# MCU_USB_v0.net
KiCad netlist of a schematic drawn in Altium Designer
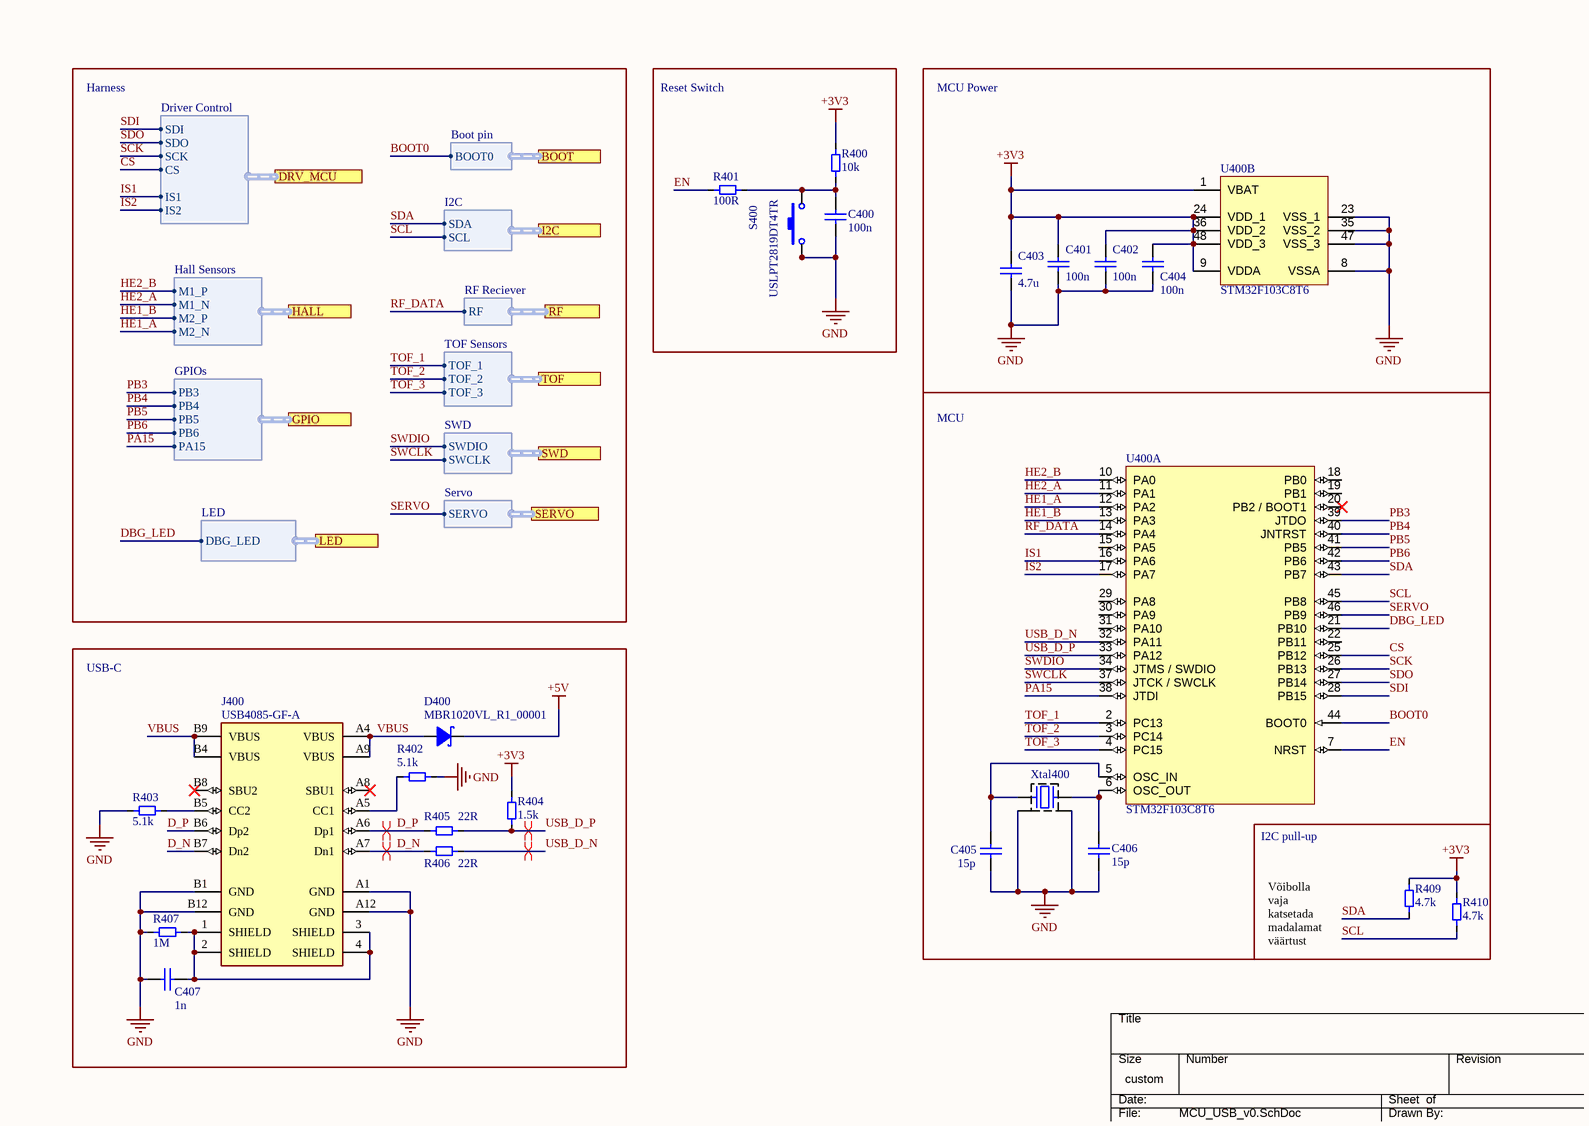
[diagram p0: MCU_USB_v0.SchDoc]

(export (version "E")
  (design (tool "Eeschema 10.0.6"))
  (components
    (comp (ref "C400")
      (value "100n")
      (footprint "MLCC_0603_M")
      (description "MLCC, 0603, 100n, 10%, 50V, X7R")
      (fields (field (name "VOLTAGE") "50V") (field (name "TOLERANCE") "10%"))
      (libsource (lib "Krakul Vault") (part "CAPACITOR_NONPOL_IEC"))
    )
    (comp (ref "C401")
      (value "100n")
      (footprint "MLCC_0603_M")
      (description "MLCC, 0603, 100n, 10%, 50V, X7R")
      (fields (field (name "VOLTAGE") "50V") (field (name "TOLERANCE") "10%"))
      (libsource (lib "Krakul Vault") (part "CAPACITOR_NONPOL_IEC"))
    )
    (comp (ref "C402")
      (value "100n")
      (footprint "MLCC_0603_M")
      (description "MLCC, 0603, 100n, 10%, 50V, X7R")
      (fields (field (name "VOLTAGE") "50V") (field (name "TOLERANCE") "10%"))
      (libsource (lib "Krakul Vault") (part "CAPACITOR_NONPOL_IEC"))
    )
    (comp (ref "C403")
      (value "4.7u")
      (footprint "MLCC_0805_M")
      (description "MLCC, 0805, 4.7u, 20%, 50V, X5R")
      (fields (field (name "MANUFACTURER") "Any") (field (name "VOLTAGE") "50V"))
      (libsource (lib "Krakul Vault") (part "CAPACITOR_NONPOL_IEC"))
    )
    (comp (ref "C404")
      (value "100n")
      (footprint "MLCC_0603_M")
      (description "MLCC, 0603, 100n, 10%, 50V, X7R")
      (fields (field (name "VOLTAGE") "50V") (field (name "TOLERANCE") "10%"))
      (libsource (lib "Krakul Vault") (part "CAPACITOR_NONPOL_IEC"))
    )
    (comp (ref "C405")
      (value "15p")
      (footprint "MLCC_0402_M")
      (description "MLCC, 0402, 15p, 10%, 25V, C0G/NP0")
      (fields (field (name "MANUFACTURER") "Any") (field (name "TOLERANCE") "10%"))
      (libsource (lib "Krakul Vault") (part "CAPACITOR_NONPOL_IEC"))
    )
    (comp (ref "C406")
      (value "15p")
      (footprint "MLCC_0402_M")
      (description "MLCC, 0402, 15p, 10%, 25V, C0G/NP0")
      (fields (field (name "MANUFACTURER") "Any") (field (name "TOLERANCE") "10%"))
      (libsource (lib "Krakul Vault") (part "CAPACITOR_NONPOL_IEC"))
    )
    (comp (ref "C407")
      (value "1n")
      (footprint "MLCC_0603_M")
      (description "MLCC, 0603, 1n, 10%, 50V, X5R")
      (fields (field (name "MANUFACTURER") "Any") (field (name "TOLERANCE") "10%"))
      (libsource (lib "Krakul Vault") (part "CAPACITOR_NONPOL_IEC"))
    )
    (comp (ref "D400")
      (value "MBR1020VL_R1_00001")
      (footprint "FP-MBR1020VL_R1_00001-MFG")
      (description "Rectifier Diode, Schottky, 1 Phase, 1 Element, 1A, 20V V(RRM), Silicon")
      (fields (field (name "MANUFACTURER") "Panjit"))
      (libsource (lib "Krakul Vault") (part "Schottky generic 2 pins"))
    )
    (comp (ref "J400")
      (value "USB4085-GF-A")
      (footprint "FP-USB4085-GF-A-MFG")
      (description "USB Connector, 16 Contact(s), Female, Right Angle, Solder Terminal, Locking, Receptacle")
      (fields (field (name "MANUFACTURER") "GCT") (field (name "PART NUMBER") "USB4800-03-A"))
      (libsource (lib "Krakul Vault") (part "USB4085-GF-A"))
    )
    (comp (ref "R400")
      (value "10k")
      (footprint "Resistor_0603_M")
      (description "Resistor, 0603, 10k, 1%, 1/10W")
      (fields (field (name "MANUFACTURER") "Any") (field (name "TOLERANCE") "1%"))
      (libsource (lib "Krakul Vault") (part "RESISTOR_GENERIC_IEC"))
    )
    (comp (ref "R401")
      (value "100R")
      (footprint "Resistor_0603_M")
      (description "Resistor, 0603, 100R, 1%, 1/10W")
      (fields (field (name "POWER") "100mW") (field (name "MANUFACTURER") "Any"))
      (libsource (lib "Krakul Vault") (part "RESISTOR_GENERIC_IEC"))
    )
    (comp (ref "R402")
      (value "5.1k")
      (footprint "Resistor_0603_M")
      (description "Resistor, 0603, 5.1k, 1%, 1/10W")
      (fields (field (name "POWER") "100mW") (field (name "MANUFACTURER") "Any"))
      (libsource (lib "Krakul Vault") (part "RESISTOR_GENERIC_IEC"))
    )
    (comp (ref "R403")
      (value "5.1k")
      (footprint "Resistor_0603_M")
      (description "Resistor, 0603, 5.1k, 1%, 1/10W")
      (fields (field (name "POWER") "100mW") (field (name "MANUFACTURER") "Any"))
      (libsource (lib "Krakul Vault") (part "RESISTOR_GENERIC_IEC"))
    )
    (comp (ref "R404")
      (value "1.5k")
      (footprint "Resistor_0603_M")
      (description "Resistor, 0603, 1.5k, 1%, 1/10W")
      (fields (field (name "MANUFACTURER") "Any") (field (name "POWER") "100mW"))
      (libsource (lib "Krakul Vault") (part "RESISTOR_GENERIC_IEC"))
    )
    (comp (ref "R405")
      (value "22R")
      (footprint "Resistor_0603_M")
      (description "Resistor, 0603, 22R, 1%, 1/10W")
      (fields (field (name "TOLERANCE") "1%") (field (name "MANUFACTURER") "Any"))
      (libsource (lib "Krakul Vault") (part "RESISTOR_GENERIC_IEC"))
    )
    (comp (ref "R406")
      (value "22R")
      (footprint "Resistor_0603_M")
      (description "Resistor, 0603, 22R, 1%, 1/10W")
      (fields (field (name "TOLERANCE") "1%") (field (name "MANUFACTURER") "Any"))
      (libsource (lib "Krakul Vault") (part "RESISTOR_GENERIC_IEC"))
    )
    (comp (ref "R407")
      (value "1M")
      (footprint "Resistor_1206_M")
      (description "Resistor, 1206, 1M, 1%, 1/4W")
      (fields (field (name "MANUFACTURER") "Any"))
      (libsource (lib "Krakul Vault") (part "RESISTOR_GENERIC_IEC"))
    )
    (comp (ref "R409")
      (value "4.7k")
      (footprint "Resistor_0603_M")
      (description "Resistor, 0603, 4.7k, 1%, 1/10W")
      (fields (field (name "MANUFACTURER") "Any") (field (name "POWER") "100mW"))
      (libsource (lib "Krakul Vault") (part "RESISTOR_GENERIC_IEC"))
    )
    (comp (ref "R410")
      (value "4.7k")
      (footprint "Resistor_0603_M")
      (description "Resistor, 0603, 4.7k, 1%, 1/10W")
      (fields (field (name "MANUFACTURER") "Any") (field (name "POWER") "100mW"))
      (libsource (lib "Krakul Vault") (part "RESISTOR_GENERIC_IEC"))
    )
    (comp (ref "S400")
      (value "USLPT2819DT4TR")
      (footprint "USLPT2819DT4TR-Footprint-1")
      (description "Keypad Switch, SPST, 0.05A, 1.96N, Solder Terminal, Panel Mount")
      (fields (field (name "MANUFACTURER") "TE Connectivity ALCOSWITCH Switches"))
      (libsource (lib "Krakul Vault") (part "Copy of Switch 4-pin"))
    )
    (comp (ref "U400")
      (value "STM32F103C8T6")
      (footprint "STM-LQFP48_M")
      (description "MCU 32-bit STM32F1 ARM Cortex M3 RISC 64KB Flash 2.5V/3.3V 48-Pin LQFP Tray")
      (fields (field (name "MANUFACTURER") "STMicroelectronics"))
      (libsource (lib "Krakul Vault") (part "MC-ARM-STM32F103X4_6-SQ48"))
    )
    (comp (ref "Xtal400")
      (value "ABM11-16.000MHZ-12-N1G-T")
      (footprint "FP-ABM11-MFG")
      (description "Crystal 16MHz ±10ppm (Tol) ±15ppm (Stability) 12pF FUND 150Ohm 4-Pin Ultra Mini-CSMD T/R")
      (fields (field (name "MANUFACTURER") "Abracon LLC") (field (name "TOLERANCE") "0.001%"))
      (libsource (lib "Krakul Vault") (part "Crystal 4 pins"))
    )
  )
  (nets
    (net (code "15") (name "+3V3") (class "Default")
      (node (ref "C401") (pin "1") (pinfunction "1_1") (pintype "passive"))
      (node (ref "C402") (pin "1") (pinfunction "1_1") (pintype "passive"))
      (node (ref "C403") (pin "2") (pinfunction "2_2") (pintype "passive"))
      (node (ref "C404") (pin "1") (pinfunction "1_1") (pintype "passive"))
      (node (ref "R400") (pin "2") (pinfunction "2_2") (pintype "passive"))
      (node (ref "R404") (pin "2") (pinfunction "2_2") (pintype "passive"))
      (node (ref "R409") (pin "2") (pinfunction "2_2") (pintype "passive"))
      (node (ref "R410") (pin "2") (pinfunction "2_2") (pintype "passive"))
      (node (ref "U400") (pin "1") (pinfunction "VBAT_1") (pintype "power_in"))
      (node (ref "U400") (pin "24") (pinfunction "VDD_1_24") (pintype "power_in"))
      (node (ref "U400") (pin "36") (pinfunction "VDD_2_36") (pintype "power_in"))
      (node (ref "U400") (pin "48") (pinfunction "VDD_3_48") (pintype "power_in"))
      (node (ref "U400") (pin "9") (pinfunction "VDDA_9") (pintype "power_in"))
    )
    (net (code "16") (name "+5V") (class "Default")
      (node (ref "D400") (pin "1") (pinfunction "C_1") (pintype "passive"))
    )
    (net (code "17") (name "/BOOT0") (class "Default")
      (node (ref "U400") (pin "44") (pinfunction "BOOT0_44") (pintype "input"))
    )
    (net (code "18") (name "/CS") (class "Default")
      (node (ref "U400") (pin "25") (pinfunction "PB12_25") (pintype "bidirectional"))
    )
    (net (code "19") (name "/DBG_LED") (class "Default")
      (node (ref "U400") (pin "21") (pinfunction "PB10_21") (pintype "bidirectional"))
    )
    (net (code "20") (name "/D_N") (class "Default")
      (node (ref "J400") (pin "A7") (pinfunction "Dn1_A7") (pintype "bidirectional"))
      (node (ref "J400") (pin "B7") (pinfunction "Dn2_B7") (pintype "bidirectional"))
      (node (ref "R406") (pin "1") (pinfunction "1_1") (pintype "passive"))
    )
    (net (code "21") (name "/D_P") (class "Default")
      (node (ref "J400") (pin "A6") (pinfunction "Dp1_A6") (pintype "bidirectional"))
      (node (ref "J400") (pin "B6") (pinfunction "Dp2_B6") (pintype "bidirectional"))
      (node (ref "R405") (pin "1") (pinfunction "1_1") (pintype "passive"))
    )
    (net (code "22") (name "/EN") (class "Default")
      (node (ref "R401") (pin "2") (pinfunction "2_2") (pintype "passive"))
      (node (ref "U400") (pin "7") (pinfunction "NRST_7") (pintype "bidirectional"))
    )
    (net (code "23") (name "/HE1_A") (class "Default")
      (node (ref "U400") (pin "12") (pinfunction "PA2_12") (pintype "bidirectional"))
    )
    (net (code "24") (name "/HE1_B") (class "Default")
      (node (ref "U400") (pin "13") (pinfunction "PA3_13") (pintype "bidirectional"))
    )
    (net (code "25") (name "/HE2_A") (class "Default")
      (node (ref "U400") (pin "11") (pinfunction "PA1_11") (pintype "bidirectional"))
    )
    (net (code "26") (name "/HE2_B") (class "Default")
      (node (ref "U400") (pin "10") (pinfunction "PA0_10") (pintype "bidirectional"))
    )
    (net (code "27") (name "/IS1") (class "Default")
      (node (ref "U400") (pin "16") (pinfunction "PA6_16") (pintype "bidirectional"))
    )
    (net (code "28") (name "/IS2") (class "Default")
      (node (ref "U400") (pin "17") (pinfunction "PA7_17") (pintype "bidirectional"))
    )
    (net (code "29") (name "/PA15") (class "Default")
      (node (ref "U400") (pin "38") (pinfunction "JTDI_38") (pintype "bidirectional"))
    )
    (net (code "30") (name "/PB3") (class "Default")
      (node (ref "U400") (pin "39") (pinfunction "JTDO_39") (pintype "bidirectional"))
    )
    (net (code "31") (name "/PB4") (class "Default")
      (node (ref "U400") (pin "40") (pinfunction "JNTRST_40") (pintype "bidirectional"))
    )
    (net (code "32") (name "/PB5") (class "Default")
      (node (ref "U400") (pin "41") (pinfunction "PB5_41") (pintype "bidirectional"))
    )
    (net (code "33") (name "/PB6") (class "Default")
      (node (ref "U400") (pin "42") (pinfunction "PB6_42") (pintype "bidirectional"))
    )
    (net (code "34") (name "/RF_DATA") (class "Default")
      (node (ref "U400") (pin "14") (pinfunction "PA4_14") (pintype "bidirectional"))
    )
    (net (code "35") (name "/SCK") (class "Default")
      (node (ref "U400") (pin "26") (pinfunction "PB13_26") (pintype "bidirectional"))
    )
    (net (code "36") (name "/SCL") (class "Default")
      (node (ref "R410") (pin "1") (pinfunction "1_1") (pintype "passive"))
      (node (ref "U400") (pin "45") (pinfunction "PB8_45") (pintype "bidirectional"))
    )
    (net (code "37") (name "/SDA") (class "Default")
      (node (ref "R409") (pin "1") (pinfunction "1_1") (pintype "passive"))
      (node (ref "U400") (pin "43") (pinfunction "PB7_43") (pintype "bidirectional"))
    )
    (net (code "38") (name "/SDI") (class "Default")
      (node (ref "U400") (pin "28") (pinfunction "PB15_28") (pintype "bidirectional"))
    )
    (net (code "39") (name "/SDO") (class "Default")
      (node (ref "U400") (pin "27") (pinfunction "PB14_27") (pintype "bidirectional"))
    )
    (net (code "40") (name "/SERVO") (class "Default")
      (node (ref "U400") (pin "46") (pinfunction "PB9_46") (pintype "bidirectional"))
    )
    (net (code "41") (name "/SWCLK") (class "Default")
      (node (ref "U400") (pin "37") (pinfunction "JTCK_/_SWCLK_37") (pintype "bidirectional"))
    )
    (net (code "42") (name "/SWDIO") (class "Default")
      (node (ref "U400") (pin "34") (pinfunction "JTMS_/_SWDIO_34") (pintype "bidirectional"))
    )
    (net (code "43") (name "/TOF_1") (class "Default")
      (node (ref "U400") (pin "2") (pinfunction "PC13_2") (pintype "bidirectional"))
    )
    (net (code "44") (name "/TOF_2") (class "Default")
      (node (ref "U400") (pin "3") (pinfunction "PC14_3") (pintype "bidirectional"))
    )
    (net (code "45") (name "/TOF_3") (class "Default")
      (node (ref "U400") (pin "4") (pinfunction "PC15_4") (pintype "bidirectional"))
    )
    (net (code "46") (name "/USB_D_N") (class "Default")
      (node (ref "R406") (pin "2") (pinfunction "2_2") (pintype "passive"))
      (node (ref "U400") (pin "32") (pinfunction "PA11_32") (pintype "bidirectional"))
    )
    (net (code "47") (name "/USB_D_P") (class "Default")
      (node (ref "R404") (pin "1") (pinfunction "1_1") (pintype "passive"))
      (node (ref "R405") (pin "2") (pinfunction "2_2") (pintype "passive"))
      (node (ref "U400") (pin "33") (pinfunction "PA12_33") (pintype "bidirectional"))
    )
    (net (code "48") (name "/VBUS") (class "Default")
      (node (ref "D400") (pin "2") (pinfunction "A_2") (pintype "passive"))
      (node (ref "J400") (pin "A4") (pinfunction "VBUS_A4") (pintype "power_in"))
      (node (ref "J400") (pin "A9") (pinfunction "VBUS_A9") (pintype "power_in"))
      (node (ref "J400") (pin "B4") (pinfunction "VBUS_B4") (pintype "power_in"))
      (node (ref "J400") (pin "B9") (pinfunction "VBUS_B9") (pintype "power_in"))
    )
    (net (code "59") (name "GND") (class "Default")
      (node (ref "C400") (pin "1") (pinfunction "1_1") (pintype "passive"))
      (node (ref "C401") (pin "2") (pinfunction "2_2") (pintype "passive"))
      (node (ref "C402") (pin "2") (pinfunction "2_2") (pintype "passive"))
      (node (ref "C403") (pin "1") (pinfunction "1_1") (pintype "passive"))
      (node (ref "C404") (pin "2") (pinfunction "2_2") (pintype "passive"))
      (node (ref "C405") (pin "1") (pinfunction "1_1") (pintype "passive"))
      (node (ref "C406") (pin "1") (pinfunction "1_1") (pintype "passive"))
      (node (ref "C407") (pin "1") (pinfunction "1_1") (pintype "passive"))
      (node (ref "J400") (pin "A1") (pinfunction "GND_A1") (pintype "power_in"))
      (node (ref "J400") (pin "A12") (pinfunction "GND_A12") (pintype "power_in"))
      (node (ref "J400") (pin "B1") (pinfunction "GND_B1") (pintype "power_in"))
      (node (ref "J400") (pin "B12") (pinfunction "GND_B12") (pintype "power_in"))
      (node (ref "R402") (pin "2") (pinfunction "2_2") (pintype "passive"))
      (node (ref "R403") (pin "1") (pinfunction "1_1") (pintype "passive"))
      (node (ref "R407") (pin "2") (pinfunction "2_2") (pintype "passive"))
      (node (ref "S400") (pin "1") (pinfunction "1_1") (pintype "passive"))
      (node (ref "S400") (pin "2") (pinfunction "2_2") (pintype "passive"))
      (node (ref "U400") (pin "23") (pinfunction "VSS_1_23") (pintype "power_in"))
      (node (ref "U400") (pin "35") (pinfunction "VSS_2_35") (pintype "power_in"))
      (node (ref "U400") (pin "47") (pinfunction "VSS_3_47") (pintype "power_in"))
      (node (ref "U400") (pin "8") (pinfunction "VSSA_8") (pintype "power_in"))
      (node (ref "Xtal400") (pin "2") (pinfunction "2_2") (pintype "power_in"))
      (node (ref "Xtal400") (pin "4") (pinfunction "4_4") (pintype "power_in"))
    )
    (net (code "60") (name "Net-(C400-Pad2)") (class "Default")
      (node (ref "C400") (pin "2") (pinfunction "2_2") (pintype "passive"))
      (node (ref "R400") (pin "1") (pinfunction "1_1") (pintype "passive"))
      (node (ref "R401") (pin "1") (pinfunction "1_1") (pintype "passive"))
      (node (ref "S400") (pin "3") (pinfunction "3_3") (pintype "passive"))
      (node (ref "S400") (pin "4") (pinfunction "4_4") (pintype "passive"))
    )
    (net (code "61") (name "Net-(C407-Pad2)") (class "Default")
      (node (ref "C407") (pin "2") (pinfunction "2_2") (pintype "passive"))
      (node (ref "J400") (pin "1") (pinfunction "SHIELD_1") (pintype "passive"))
      (node (ref "J400") (pin "2") (pinfunction "SHIELD_2") (pintype "passive"))
      (node (ref "J400") (pin "3") (pinfunction "SHIELD_3") (pintype "passive"))
      (node (ref "J400") (pin "4") (pinfunction "SHIELD_4") (pintype "passive"))
      (node (ref "R407") (pin "1") (pinfunction "1_1") (pintype "passive"))
    )
    (net (code "62") (name "Net-(J400-CC1)") (class "Default")
      (node (ref "J400") (pin "A5") (pinfunction "CC1_A5") (pintype "bidirectional"))
      (node (ref "R402") (pin "1") (pinfunction "1_1") (pintype "passive"))
    )
    (net (code "63") (name "Net-(J400-CC2)") (class "Default")
      (node (ref "J400") (pin "B5") (pinfunction "CC2_B5") (pintype "bidirectional"))
      (node (ref "R403") (pin "2") (pinfunction "2_2") (pintype "passive"))
    )
    (net (code "64") (name "Net-(U400A-OSC_IN)") (class "Default")
      (node (ref "C405") (pin "2") (pinfunction "2_2") (pintype "passive"))
      (node (ref "U400") (pin "5") (pinfunction "OSC_IN_5") (pintype "bidirectional"))
      (node (ref "Xtal400") (pin "1") (pinfunction "1_1") (pintype "passive"))
    )
    (net (code "65") (name "Net-(U400A-OSC_OUT)") (class "Default")
      (node (ref "C406") (pin "2") (pinfunction "2_2") (pintype "passive"))
      (node (ref "U400") (pin "6") (pinfunction "OSC_OUT_6") (pintype "bidirectional"))
      (node (ref "Xtal400") (pin "3") (pinfunction "3_3") (pintype "passive"))
    )
    (net (code "66") (name "unconnected-(J400-SBU1-PadA8)") (class "Default")
      (node (ref "J400") (pin "A8") (pinfunction "SBU1_A8") (pintype "bidirectional+no_connect"))
    )
    (net (code "67") (name "unconnected-(J400-SBU2-PadB8)") (class "Default")
      (node (ref "J400") (pin "B8") (pinfunction "SBU2_B8") (pintype "bidirectional+no_connect"))
    )
    (net (code "68") (name "unconnected-(U400A-PA5-Pad15)") (class "Default")
      (node (ref "U400") (pin "15") (pinfunction "PA5_15") (pintype "bidirectional"))
    )
    (net (code "69") (name "unconnected-(U400A-PA8-Pad29)") (class "Default")
      (node (ref "U400") (pin "29") (pinfunction "PA8_29") (pintype "bidirectional"))
    )
    (net (code "70") (name "unconnected-(U400A-PA9-Pad30)") (class "Default")
      (node (ref "U400") (pin "30") (pinfunction "PA9_30") (pintype "bidirectional"))
    )
    (net (code "71") (name "unconnected-(U400A-PA10-Pad31)") (class "Default")
      (node (ref "U400") (pin "31") (pinfunction "PA10_31") (pintype "bidirectional"))
    )
    (net (code "72") (name "unconnected-(U400A-PB0-Pad18)") (class "Default")
      (node (ref "U400") (pin "18") (pinfunction "PB0_18") (pintype "bidirectional"))
    )
    (net (code "73") (name "unconnected-(U400A-PB1-Pad19)") (class "Default")
      (node (ref "U400") (pin "19") (pinfunction "PB1_19") (pintype "bidirectional"))
    )
    (net (code "74") (name "unconnected-(U400A-PB2_{slash}_BOOT1-Pad20)") (class "Default")
      (node (ref "U400") (pin "20") (pinfunction "PB2_/_BOOT1_20") (pintype "bidirectional+no_connect"))
    )
    (net (code "75") (name "unconnected-(U400A-PB11-Pad22)") (class "Default")
      (node (ref "U400") (pin "22") (pinfunction "PB11_22") (pintype "bidirectional"))
    )
  )
)
